# mux_board_final.net
KiCad netlist of a schematic drawn in EAGLE
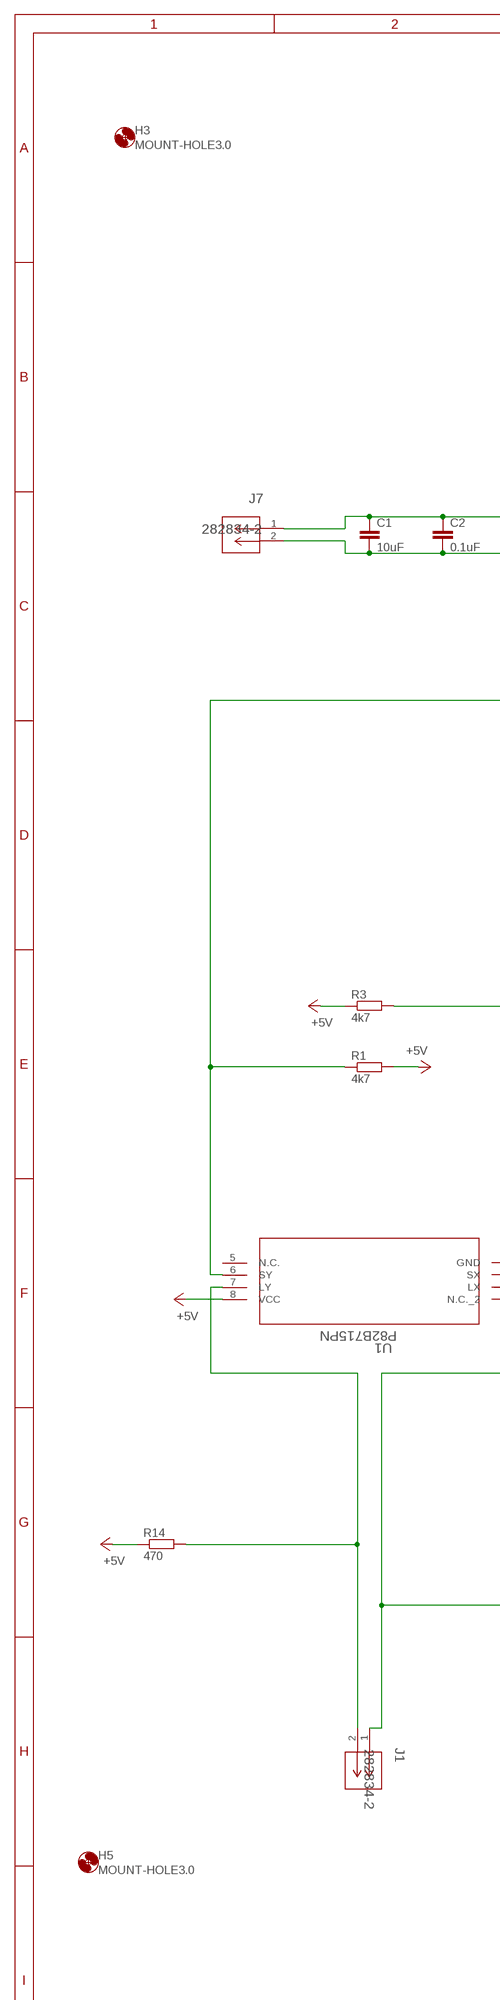
[diagram p0: schematic, sheet 1, part 1 of 2]
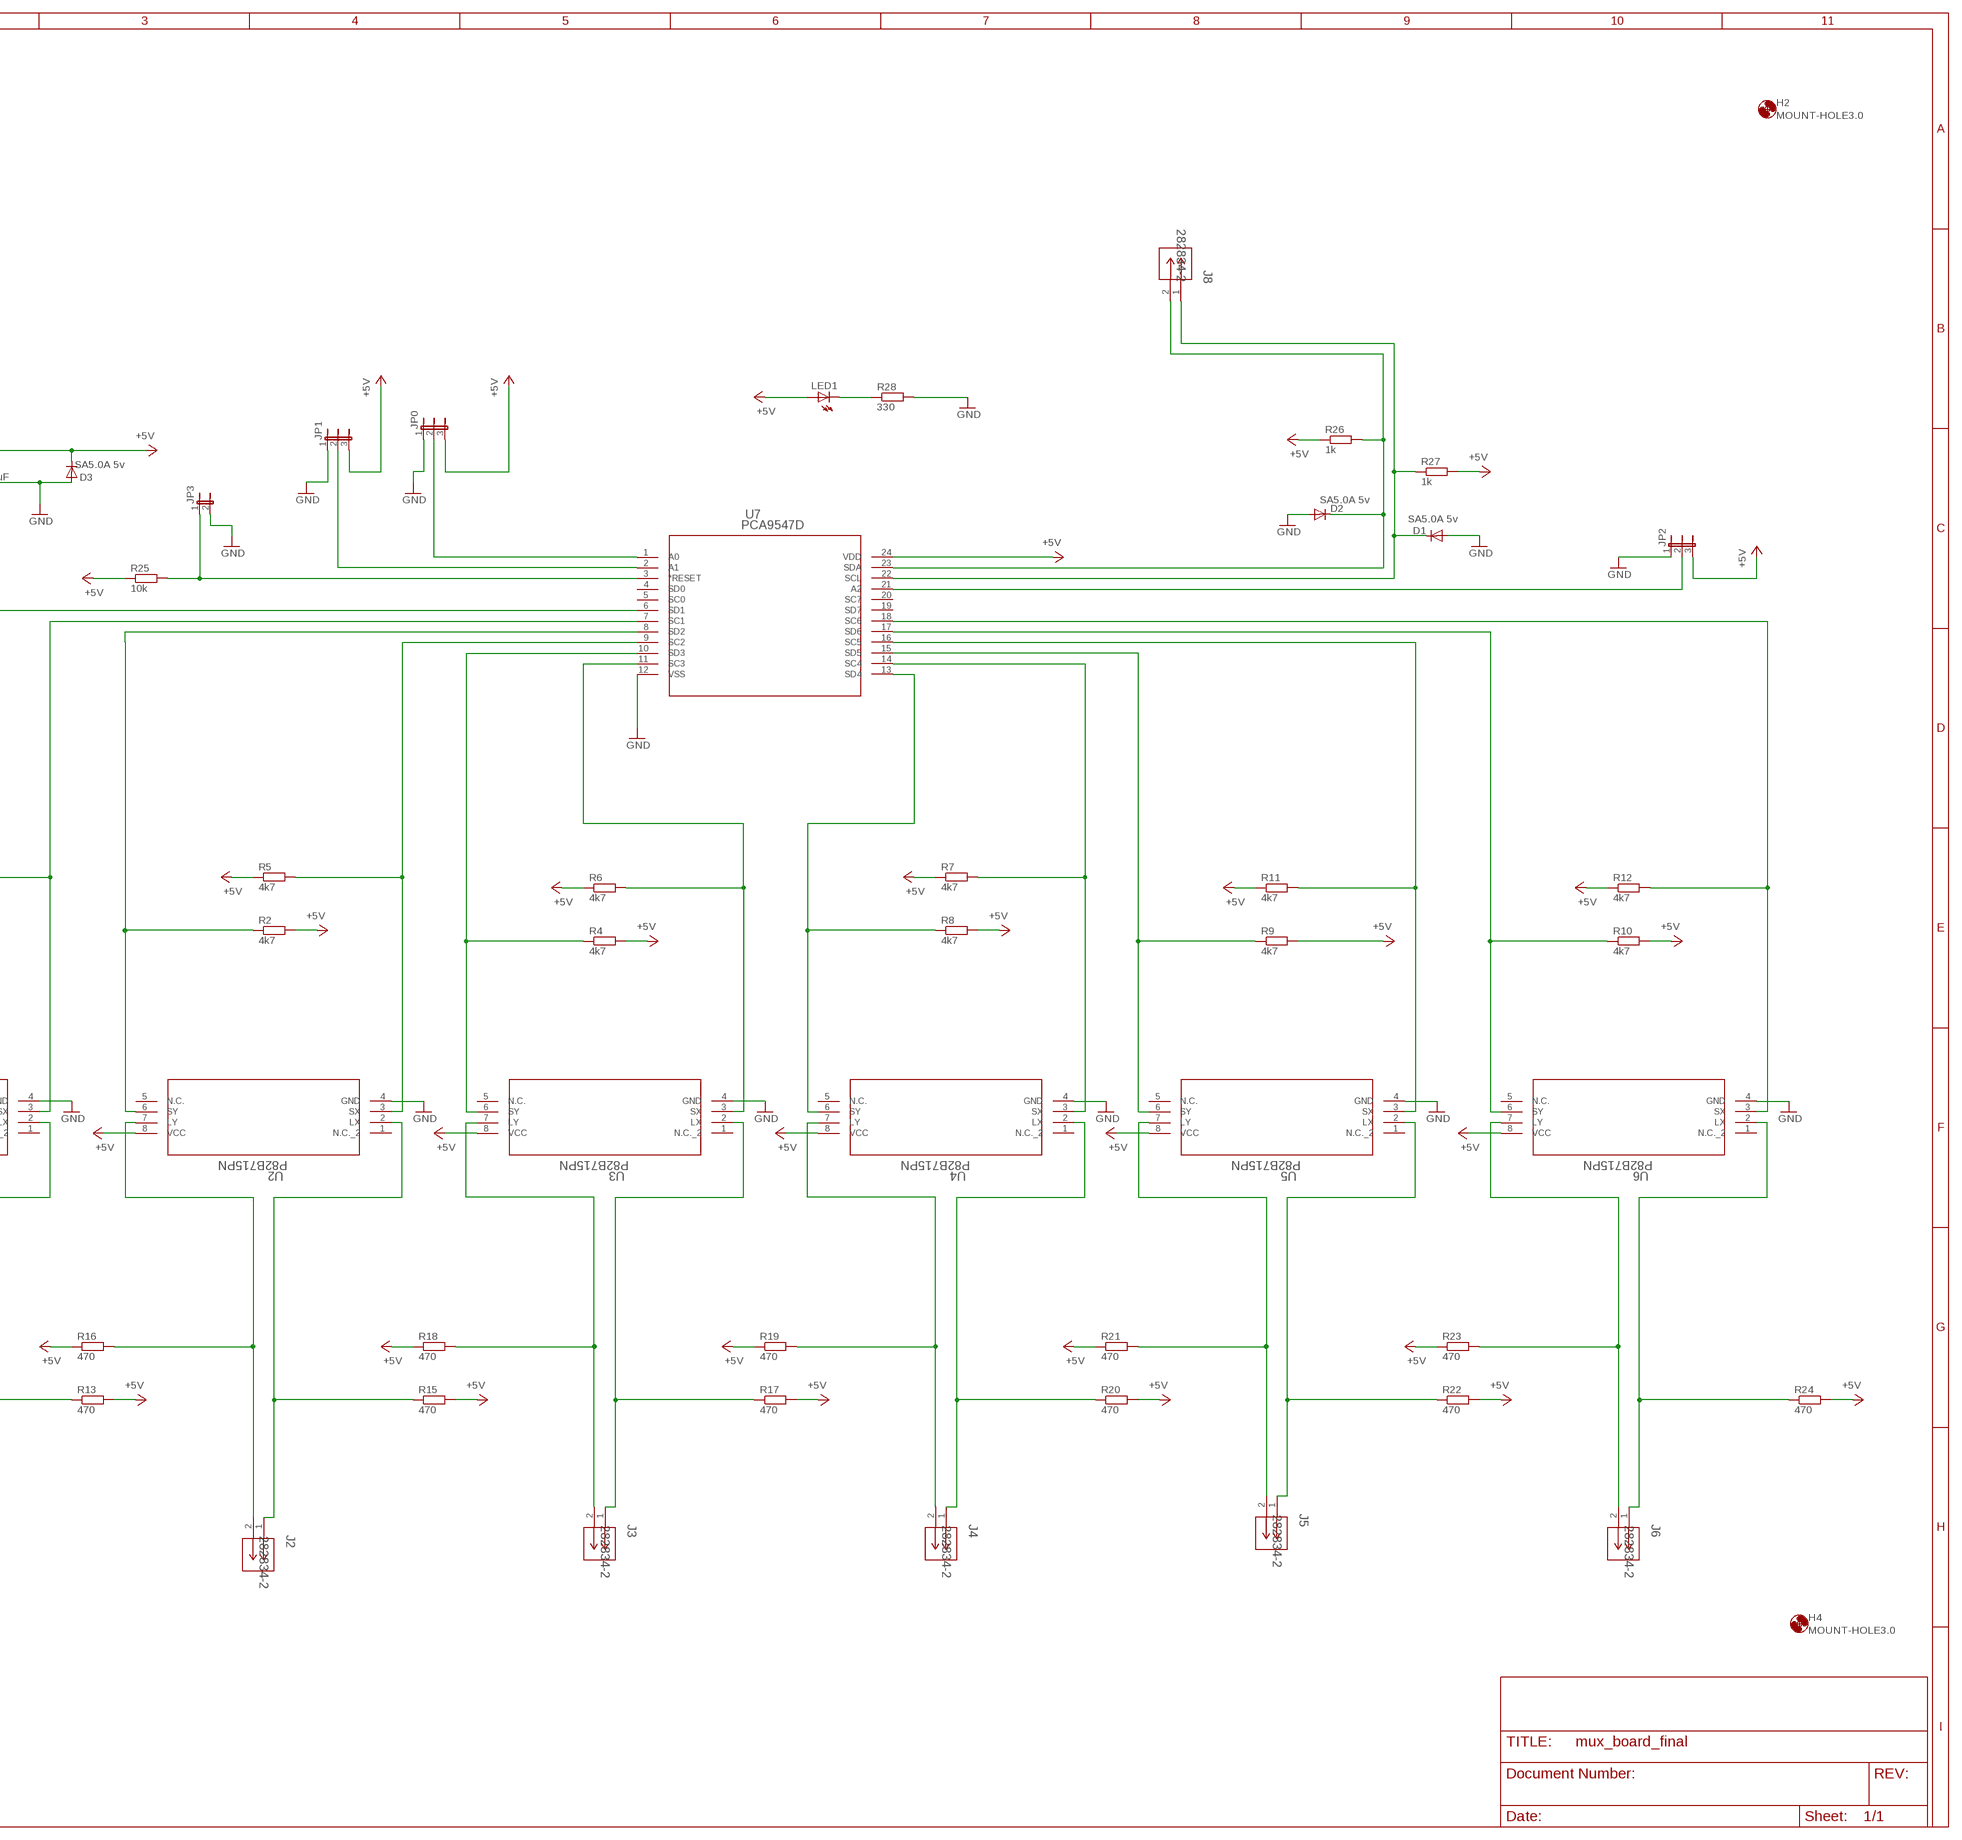
[diagram p1: schematic, sheet 1, part 2 of 2]

(export (version "E")
  (design (tool "Eeschema 10.0.6"))
  (components
    (comp (ref "C1")
      (value "10uF")
      (footprint "eagle-import:C025-025X050")
      (libsource (lib "eagle-import") (part "C-EU025-025X050"))
    )
    (comp (ref "C2")
      (value "0.1uF")
      (footprint "eagle-import:C025-025X050")
      (libsource (lib "eagle-import") (part "C-EU025-025X050"))
    )
    (comp (ref "D1")
      (value "SA5.0A 5v")
      (footprint "eagle-import:DO41-10")
      (libsource (lib "eagle-import") (part "1N4004"))
    )
    (comp (ref "D2")
      (value "SA5.0A 5v")
      (footprint "eagle-import:DO41-10")
      (libsource (lib "eagle-import") (part "1N4004"))
    )
    (comp (ref "D3")
      (value "SA5.0A 5v")
      (footprint "eagle-import:DO41-10")
      (libsource (lib "eagle-import") (part "1N4004"))
    )
    (comp (ref "H2")
      (value "MOUNT-HOLE3.0")
      (footprint "eagle-import:3,0")
      (libsource (lib "eagle-import") (part "MOUNT-HOLE3.0"))
    )
    (comp (ref "H3")
      (value "MOUNT-HOLE3.0")
      (footprint "eagle-import:3,0")
      (libsource (lib "eagle-import") (part "MOUNT-HOLE3.0"))
    )
    (comp (ref "H4")
      (value "MOUNT-HOLE3.0")
      (footprint "eagle-import:3,0")
      (libsource (lib "eagle-import") (part "MOUNT-HOLE3.0"))
    )
    (comp (ref "H5")
      (value "MOUNT-HOLE3.0")
      (footprint "eagle-import:3,0")
      (libsource (lib "eagle-import") (part "MOUNT-HOLE3.0"))
    )
    (comp (ref "J1")
      (value "282834-2")
      (footprint "eagle-import:CONN_282834-2")
      (fields (field (name "RSPARTNUMBER") "7100104"))
      (libsource (lib "eagle-import") (part "282834-2"))
    )
    (comp (ref "J2")
      (value "282834-2")
      (footprint "eagle-import:CONN_282834-2")
      (fields (field (name "RSPARTNUMBER") "7100104"))
      (libsource (lib "eagle-import") (part "282834-2"))
    )
    (comp (ref "J3")
      (value "282834-2")
      (footprint "eagle-import:CONN_282834-2")
      (fields (field (name "RSPARTNUMBER") "7100104"))
      (libsource (lib "eagle-import") (part "282834-2"))
    )
    (comp (ref "J4")
      (value "282834-2")
      (footprint "eagle-import:CONN_282834-2")
      (fields (field (name "RSPARTNUMBER") "7100104"))
      (libsource (lib "eagle-import") (part "282834-2"))
    )
    (comp (ref "J5")
      (value "282834-2")
      (footprint "eagle-import:CONN_282834-2")
      (fields (field (name "RSPARTNUMBER") "7100104"))
      (libsource (lib "eagle-import") (part "282834-2"))
    )
    (comp (ref "J6")
      (value "282834-2")
      (footprint "eagle-import:CONN_282834-2")
      (fields (field (name "RSPARTNUMBER") "7100104"))
      (libsource (lib "eagle-import") (part "282834-2"))
    )
    (comp (ref "J7")
      (value "282834-2")
      (footprint "eagle-import:CONN_282834-2")
      (fields (field (name "RSPARTNUMBER") "7100104"))
      (libsource (lib "eagle-import") (part "282834-2"))
    )
    (comp (ref "J8")
      (value "282834-2")
      (footprint "eagle-import:CONN_282834-2")
      (fields (field (name "RSPARTNUMBER") "7100104"))
      (libsource (lib "eagle-import") (part "282834-2"))
    )
    (comp (ref "JP0")
      (value "JP2E")
      (footprint "eagle-import:JP2")
      (libsource (lib "eagle-import") (part "JP2E"))
    )
    (comp (ref "JP1")
      (value "JP2E")
      (footprint "eagle-import:JP2")
      (libsource (lib "eagle-import") (part "JP2E"))
    )
    (comp (ref "JP2")
      (value "JP2E")
      (footprint "eagle-import:JP2")
      (libsource (lib "eagle-import") (part "JP2E"))
    )
    (comp (ref "JP3")
      (value "JP1E")
      (footprint "eagle-import:JP1")
      (libsource (lib "eagle-import") (part "JP1E"))
    )
    (comp (ref "LED1")
      (value "LED3MM")
      (footprint "eagle-import:LED3MM")
      (libsource (lib "eagle-import") (part "LED3MM"))
    )
    (comp (ref "R1")
      (value "4k7")
      (footprint "eagle-import:0204_7")
      (libsource (lib "eagle-import") (part "R-EU_0204/7"))
    )
    (comp (ref "R2")
      (value "4k7")
      (footprint "eagle-import:0204_7")
      (libsource (lib "eagle-import") (part "R-EU_0204/7"))
    )
    (comp (ref "R3")
      (value "4k7")
      (footprint "eagle-import:0204_7")
      (libsource (lib "eagle-import") (part "R-EU_0204/7"))
    )
    (comp (ref "R4")
      (value "4k7")
      (footprint "eagle-import:0204_7")
      (libsource (lib "eagle-import") (part "R-EU_0204/7"))
    )
    (comp (ref "R5")
      (value "4k7")
      (footprint "eagle-import:0204_7")
      (libsource (lib "eagle-import") (part "R-EU_0204/7"))
    )
    (comp (ref "R6")
      (value "4k7")
      (footprint "eagle-import:0204_7")
      (libsource (lib "eagle-import") (part "R-EU_0204/7"))
    )
    (comp (ref "R7")
      (value "4k7")
      (footprint "eagle-import:0204_7")
      (libsource (lib "eagle-import") (part "R-EU_0204/7"))
    )
    (comp (ref "R8")
      (value "4k7")
      (footprint "eagle-import:0204_7")
      (libsource (lib "eagle-import") (part "R-EU_0204/7"))
    )
    (comp (ref "R9")
      (value "4k7")
      (footprint "eagle-import:0204_7")
      (libsource (lib "eagle-import") (part "R-EU_0204/7"))
    )
    (comp (ref "R10")
      (value "4k7")
      (footprint "eagle-import:0204_7")
      (libsource (lib "eagle-import") (part "R-EU_0204/7"))
    )
    (comp (ref "R11")
      (value "4k7")
      (footprint "eagle-import:0204_7")
      (libsource (lib "eagle-import") (part "R-EU_0204/7"))
    )
    (comp (ref "R12")
      (value "4k7")
      (footprint "eagle-import:0204_7")
      (libsource (lib "eagle-import") (part "R-EU_0204/7"))
    )
    (comp (ref "R13")
      (value "470")
      (footprint "eagle-import:0204_7")
      (libsource (lib "eagle-import") (part "R-EU_0204/7"))
    )
    (comp (ref "R14")
      (value "470")
      (footprint "eagle-import:0204_7")
      (libsource (lib "eagle-import") (part "R-EU_0204/7"))
    )
    (comp (ref "R15")
      (value "470")
      (footprint "eagle-import:0204_7")
      (libsource (lib "eagle-import") (part "R-EU_0204/7"))
    )
    (comp (ref "R16")
      (value "470")
      (footprint "eagle-import:0204_7")
      (libsource (lib "eagle-import") (part "R-EU_0204/7"))
    )
    (comp (ref "R17")
      (value "470")
      (footprint "eagle-import:0204_7")
      (libsource (lib "eagle-import") (part "R-EU_0204/7"))
    )
    (comp (ref "R18")
      (value "470")
      (footprint "eagle-import:0204_7")
      (libsource (lib "eagle-import") (part "R-EU_0204/7"))
    )
    (comp (ref "R19")
      (value "470")
      (footprint "eagle-import:0204_7")
      (libsource (lib "eagle-import") (part "R-EU_0204/7"))
    )
    (comp (ref "R20")
      (value "470")
      (footprint "eagle-import:0204_7")
      (libsource (lib "eagle-import") (part "R-EU_0204/7"))
    )
    (comp (ref "R21")
      (value "470")
      (footprint "eagle-import:0204_7")
      (libsource (lib "eagle-import") (part "R-EU_0204/7"))
    )
    (comp (ref "R22")
      (value "470")
      (footprint "eagle-import:0204_7")
      (libsource (lib "eagle-import") (part "R-EU_0204/7"))
    )
    (comp (ref "R23")
      (value "470")
      (footprint "eagle-import:0204_7")
      (libsource (lib "eagle-import") (part "R-EU_0204/7"))
    )
    (comp (ref "R24")
      (value "470")
      (footprint "eagle-import:0204_7")
      (libsource (lib "eagle-import") (part "R-EU_0204/7"))
    )
    (comp (ref "R25")
      (value "10k")
      (footprint "eagle-import:0204_7")
      (libsource (lib "eagle-import") (part "R-EU_0204/7"))
    )
    (comp (ref "R26")
      (value "1k")
      (footprint "eagle-import:0204_7")
      (libsource (lib "eagle-import") (part "R-EU_0204/7"))
    )
    (comp (ref "R27")
      (value "1k")
      (footprint "eagle-import:0204_7")
      (libsource (lib "eagle-import") (part "R-EU_0204/7"))
    )
    (comp (ref "R28")
      (value "330")
      (footprint "eagle-import:0204_7")
      (libsource (lib "eagle-import") (part "R-EU_0204/7"))
    )
    (comp (ref "U1")
      (value "P82B715PN")
      (footprint "eagle-import:SOT97-1")
      (fields (field (name "RSPARTNUMBER") "821784"))
      (libsource (lib "eagle-import") (part "P82B715PN"))
    )
    (comp (ref "U2")
      (value "P82B715PN")
      (footprint "eagle-import:SOT97-1")
      (fields (field (name "RSPARTNUMBER") "821784"))
      (libsource (lib "eagle-import") (part "P82B715PN"))
    )
    (comp (ref "U3")
      (value "P82B715PN")
      (footprint "eagle-import:SOT97-1")
      (fields (field (name "RSPARTNUMBER") "821784"))
      (libsource (lib "eagle-import") (part "P82B715PN"))
    )
    (comp (ref "U4")
      (value "P82B715PN")
      (footprint "eagle-import:SOT97-1")
      (fields (field (name "RSPARTNUMBER") "821784"))
      (libsource (lib "eagle-import") (part "P82B715PN"))
    )
    (comp (ref "U5")
      (value "P82B715PN")
      (footprint "eagle-import:SOT97-1")
      (fields (field (name "RSPARTNUMBER") "821784"))
      (libsource (lib "eagle-import") (part "P82B715PN"))
    )
    (comp (ref "U6")
      (value "P82B715PN")
      (footprint "eagle-import:SOT97-1")
      (fields (field (name "RSPARTNUMBER") "821784"))
      (libsource (lib "eagle-import") (part "P82B715PN"))
    )
    (comp (ref "U7")
      (value "PCA9547D")
      (footprint "eagle-import:SOT137-1")
      (fields (field (name "RSPARTNUMBER") "7258877"))
      (libsource (lib "eagle-import") (part "PCA9547D"))
    )
  )
  (nets
    (net (code "1") (name "+5V") (class "Default")
      (node (ref "C1") (pin "1") (pinfunction "1_1") (pintype "passive"))
      (node (ref "C2") (pin "1") (pinfunction "1_1") (pintype "passive"))
      (node (ref "D3") (pin "C") (pinfunction "C_C") (pintype "passive"))
      (node (ref "J7") (pin "1") (pinfunction "1_1") (pintype "passive"))
      (node (ref "JP0") (pin "3") (pinfunction "3_3") (pintype "passive"))
      (node (ref "JP1") (pin "3") (pinfunction "3_3") (pintype "passive"))
      (node (ref "JP2") (pin "3") (pinfunction "3_3") (pintype "passive"))
      (node (ref "LED1") (pin "A") (pinfunction "A_A") (pintype "passive"))
      (node (ref "R1") (pin "2") (pinfunction "2_2") (pintype "passive"))
      (node (ref "R10") (pin "2") (pinfunction "2_2") (pintype "passive"))
      (node (ref "R11") (pin "1") (pinfunction "1_1") (pintype "passive"))
      (node (ref "R12") (pin "1") (pinfunction "1_1") (pintype "passive"))
      (node (ref "R13") (pin "2") (pinfunction "2_2") (pintype "passive"))
      (node (ref "R14") (pin "1") (pinfunction "1_1") (pintype "passive"))
      (node (ref "R15") (pin "2") (pinfunction "2_2") (pintype "passive"))
      (node (ref "R16") (pin "1") (pinfunction "1_1") (pintype "passive"))
      (node (ref "R17") (pin "2") (pinfunction "2_2") (pintype "passive"))
      (node (ref "R18") (pin "1") (pinfunction "1_1") (pintype "passive"))
      (node (ref "R19") (pin "1") (pinfunction "1_1") (pintype "passive"))
      (node (ref "R2") (pin "2") (pinfunction "2_2") (pintype "passive"))
      (node (ref "R20") (pin "2") (pinfunction "2_2") (pintype "passive"))
      (node (ref "R21") (pin "1") (pinfunction "1_1") (pintype "passive"))
      (node (ref "R22") (pin "2") (pinfunction "2_2") (pintype "passive"))
      (node (ref "R23") (pin "1") (pinfunction "1_1") (pintype "passive"))
      (node (ref "R24") (pin "2") (pinfunction "2_2") (pintype "passive"))
      (node (ref "R25") (pin "1") (pinfunction "1_1") (pintype "passive"))
      (node (ref "R26") (pin "1") (pinfunction "1_1") (pintype "passive"))
      (node (ref "R27") (pin "2") (pinfunction "2_2") (pintype "passive"))
      (node (ref "R3") (pin "1") (pinfunction "1_1") (pintype "passive"))
      (node (ref "R4") (pin "2") (pinfunction "2_2") (pintype "passive"))
      (node (ref "R5") (pin "1") (pinfunction "1_1") (pintype "passive"))
      (node (ref "R6") (pin "1") (pinfunction "1_1") (pintype "passive"))
      (node (ref "R7") (pin "1") (pinfunction "1_1") (pintype "passive"))
      (node (ref "R8") (pin "2") (pinfunction "2_2") (pintype "passive"))
      (node (ref "R9") (pin "2") (pinfunction "2_2") (pintype "passive"))
      (node (ref "U1") (pin "8") (pinfunction "VCC_8") (pintype "passive"))
      (node (ref "U2") (pin "8") (pinfunction "VCC_8") (pintype "passive"))
      (node (ref "U3") (pin "8") (pinfunction "VCC_8") (pintype "passive"))
      (node (ref "U4") (pin "8") (pinfunction "VCC_8") (pintype "passive"))
      (node (ref "U5") (pin "8") (pinfunction "VCC_8") (pintype "passive"))
      (node (ref "U6") (pin "8") (pinfunction "VCC_8") (pintype "passive"))
      (node (ref "U7") (pin "24") (pinfunction "VDD_24") (pintype "passive"))
    )
    (net (code "2") (name "GND") (class "Default")
      (node (ref "C1") (pin "2") (pinfunction "2_2") (pintype "passive"))
      (node (ref "C2") (pin "2") (pinfunction "2_2") (pintype "passive"))
      (node (ref "D1") (pin "A") (pinfunction "A_A") (pintype "passive"))
      (node (ref "D2") (pin "A") (pinfunction "A_A") (pintype "passive"))
      (node (ref "D3") (pin "A") (pinfunction "A_A") (pintype "passive"))
      (node (ref "J7") (pin "2") (pinfunction "2_2") (pintype "passive"))
      (node (ref "JP0") (pin "1") (pinfunction "1_1") (pintype "passive"))
      (node (ref "JP1") (pin "1") (pinfunction "1_1") (pintype "passive"))
      (node (ref "JP2") (pin "1") (pinfunction "1_1") (pintype "passive"))
      (node (ref "JP3") (pin "2") (pinfunction "2_2") (pintype "passive"))
      (node (ref "R28") (pin "2") (pinfunction "2_2") (pintype "passive"))
      (node (ref "U1") (pin "4") (pinfunction "GND_4") (pintype "passive"))
      (node (ref "U2") (pin "4") (pinfunction "GND_4") (pintype "passive"))
      (node (ref "U3") (pin "4") (pinfunction "GND_4") (pintype "passive"))
      (node (ref "U4") (pin "4") (pinfunction "GND_4") (pintype "passive"))
      (node (ref "U5") (pin "4") (pinfunction "GND_4") (pintype "passive"))
      (node (ref "U6") (pin "4") (pinfunction "GND_4") (pintype "passive"))
      (node (ref "U7") (pin "12") (pinfunction "VSS_12") (pintype "passive"))
    )
    (net (code "3") (name "Net-(LED1-C)") (class "Default")
      (node (ref "LED1") (pin "K") (pinfunction "C_K") (pintype "passive"))
      (node (ref "R28") (pin "1") (pinfunction "1_1") (pintype "passive"))
    )
    (net (code "4") (name "Net-(U1-LX)") (class "Default")
      (node (ref "J1") (pin "1") (pinfunction "1_1") (pintype "passive"))
      (node (ref "R13") (pin "1") (pinfunction "1_1") (pintype "passive"))
      (node (ref "U1") (pin "2") (pinfunction "LX_2") (pintype "passive"))
    )
    (net (code "5") (name "Net-(U1-LY)") (class "Default")
      (node (ref "J1") (pin "2") (pinfunction "2_2") (pintype "passive"))
      (node (ref "R14") (pin "2") (pinfunction "2_2") (pintype "passive"))
      (node (ref "U1") (pin "7") (pinfunction "LY_7") (pintype "passive"))
    )
    (net (code "6") (name "Net-(U1-SX)") (class "Default")
      (node (ref "R3") (pin "2") (pinfunction "2_2") (pintype "passive"))
      (node (ref "U1") (pin "3") (pinfunction "SX_3") (pintype "passive"))
      (node (ref "U7") (pin "7") (pinfunction "SC1_7") (pintype "passive"))
    )
    (net (code "7") (name "Net-(U1-SY)") (class "Default")
      (node (ref "R1") (pin "1") (pinfunction "1_1") (pintype "passive"))
      (node (ref "U1") (pin "6") (pinfunction "SY_6") (pintype "passive"))
      (node (ref "U7") (pin "6") (pinfunction "SD1_6") (pintype "passive"))
    )
    (net (code "8") (name "Net-(U2-LX)") (class "Default")
      (node (ref "J2") (pin "1") (pinfunction "1_1") (pintype "passive"))
      (node (ref "R15") (pin "1") (pinfunction "1_1") (pintype "passive"))
      (node (ref "U2") (pin "2") (pinfunction "LX_2") (pintype "passive"))
    )
    (net (code "9") (name "Net-(U2-LY)") (class "Default")
      (node (ref "J2") (pin "2") (pinfunction "2_2") (pintype "passive"))
      (node (ref "R16") (pin "2") (pinfunction "2_2") (pintype "passive"))
      (node (ref "U2") (pin "7") (pinfunction "LY_7") (pintype "passive"))
    )
    (net (code "10") (name "Net-(U2-SX)") (class "Default")
      (node (ref "R5") (pin "2") (pinfunction "2_2") (pintype "passive"))
      (node (ref "U2") (pin "3") (pinfunction "SX_3") (pintype "passive"))
      (node (ref "U7") (pin "9") (pinfunction "SC2_9") (pintype "passive"))
    )
    (net (code "11") (name "Net-(U2-SY)") (class "Default")
      (node (ref "R2") (pin "1") (pinfunction "1_1") (pintype "passive"))
      (node (ref "U2") (pin "6") (pinfunction "SY_6") (pintype "passive"))
      (node (ref "U7") (pin "8") (pinfunction "SD2_8") (pintype "passive"))
    )
    (net (code "12") (name "Net-(U3-LX)") (class "Default")
      (node (ref "J3") (pin "1") (pinfunction "1_1") (pintype "passive"))
      (node (ref "R17") (pin "1") (pinfunction "1_1") (pintype "passive"))
      (node (ref "U3") (pin "2") (pinfunction "LX_2") (pintype "passive"))
    )
    (net (code "13") (name "Net-(U3-LY)") (class "Default")
      (node (ref "J3") (pin "2") (pinfunction "2_2") (pintype "passive"))
      (node (ref "R18") (pin "2") (pinfunction "2_2") (pintype "passive"))
      (node (ref "U3") (pin "7") (pinfunction "LY_7") (pintype "passive"))
    )
    (net (code "14") (name "Net-(U3-SX)") (class "Default")
      (node (ref "R6") (pin "2") (pinfunction "2_2") (pintype "passive"))
      (node (ref "U3") (pin "3") (pinfunction "SX_3") (pintype "passive"))
      (node (ref "U7") (pin "11") (pinfunction "SC3_11") (pintype "passive"))
    )
    (net (code "15") (name "Net-(U3-SY)") (class "Default")
      (node (ref "R4") (pin "1") (pinfunction "1_1") (pintype "passive"))
      (node (ref "U3") (pin "6") (pinfunction "SY_6") (pintype "passive"))
      (node (ref "U7") (pin "10") (pinfunction "SD3_10") (pintype "passive"))
    )
    (net (code "16") (name "Net-(U4-LX)") (class "Default")
      (node (ref "J4") (pin "1") (pinfunction "1_1") (pintype "passive"))
      (node (ref "R20") (pin "1") (pinfunction "1_1") (pintype "passive"))
      (node (ref "U4") (pin "2") (pinfunction "LX_2") (pintype "passive"))
    )
    (net (code "17") (name "Net-(U4-LY)") (class "Default")
      (node (ref "J4") (pin "2") (pinfunction "2_2") (pintype "passive"))
      (node (ref "R19") (pin "2") (pinfunction "2_2") (pintype "passive"))
      (node (ref "U4") (pin "7") (pinfunction "LY_7") (pintype "passive"))
    )
    (net (code "18") (name "Net-(U4-SX)") (class "Default")
      (node (ref "R7") (pin "2") (pinfunction "2_2") (pintype "passive"))
      (node (ref "U4") (pin "3") (pinfunction "SX_3") (pintype "passive"))
      (node (ref "U7") (pin "14") (pinfunction "SC4_14") (pintype "passive"))
    )
    (net (code "19") (name "Net-(U4-SY)") (class "Default")
      (node (ref "R8") (pin "1") (pinfunction "1_1") (pintype "passive"))
      (node (ref "U4") (pin "6") (pinfunction "SY_6") (pintype "passive"))
      (node (ref "U7") (pin "13") (pinfunction "SD4_13") (pintype "passive"))
    )
    (net (code "20") (name "Net-(U5-LX)") (class "Default")
      (node (ref "J5") (pin "1") (pinfunction "1_1") (pintype "passive"))
      (node (ref "R22") (pin "1") (pinfunction "1_1") (pintype "passive"))
      (node (ref "U5") (pin "2") (pinfunction "LX_2") (pintype "passive"))
    )
    (net (code "21") (name "Net-(U5-LY)") (class "Default")
      (node (ref "J5") (pin "2") (pinfunction "2_2") (pintype "passive"))
      (node (ref "R21") (pin "2") (pinfunction "2_2") (pintype "passive"))
      (node (ref "U5") (pin "7") (pinfunction "LY_7") (pintype "passive"))
    )
    (net (code "22") (name "Net-(U5-SX)") (class "Default")
      (node (ref "R11") (pin "2") (pinfunction "2_2") (pintype "passive"))
      (node (ref "U5") (pin "3") (pinfunction "SX_3") (pintype "passive"))
      (node (ref "U7") (pin "16") (pinfunction "SC5_16") (pintype "passive"))
    )
    (net (code "23") (name "Net-(U5-SY)") (class "Default")
      (node (ref "R9") (pin "1") (pinfunction "1_1") (pintype "passive"))
      (node (ref "U5") (pin "6") (pinfunction "SY_6") (pintype "passive"))
      (node (ref "U7") (pin "15") (pinfunction "SD5_15") (pintype "passive"))
    )
    (net (code "24") (name "Net-(U6-LX)") (class "Default")
      (node (ref "J6") (pin "1") (pinfunction "1_1") (pintype "passive"))
      (node (ref "R24") (pin "1") (pinfunction "1_1") (pintype "passive"))
      (node (ref "U6") (pin "2") (pinfunction "LX_2") (pintype "passive"))
    )
    (net (code "25") (name "Net-(U6-LY)") (class "Default")
      (node (ref "J6") (pin "2") (pinfunction "2_2") (pintype "passive"))
      (node (ref "R23") (pin "2") (pinfunction "2_2") (pintype "passive"))
      (node (ref "U6") (pin "7") (pinfunction "LY_7") (pintype "passive"))
    )
    (net (code "26") (name "Net-(U6-SX)") (class "Default")
      (node (ref "R12") (pin "2") (pinfunction "2_2") (pintype "passive"))
      (node (ref "U6") (pin "3") (pinfunction "SX_3") (pintype "passive"))
      (node (ref "U7") (pin "18") (pinfunction "SC6_18") (pintype "passive"))
    )
    (net (code "27") (name "Net-(U6-SY)") (class "Default")
      (node (ref "R10") (pin "1") (pinfunction "1_1") (pintype "passive"))
      (node (ref "U6") (pin "6") (pinfunction "SY_6") (pintype "passive"))
      (node (ref "U7") (pin "17") (pinfunction "SD6_17") (pintype "passive"))
    )
    (net (code "28") (name "Net-(U7-*RESET)") (class "Default")
      (node (ref "JP3") (pin "1") (pinfunction "1_1") (pintype "passive"))
      (node (ref "R25") (pin "2") (pinfunction "2_2") (pintype "passive"))
      (node (ref "U7") (pin "3") (pinfunction "*RESET_3") (pintype "passive"))
    )
    (net (code "29") (name "Net-(U7-A0)") (class "Default")
      (node (ref "JP0") (pin "2") (pinfunction "2_2") (pintype "passive"))
      (node (ref "U7") (pin "1") (pinfunction "A0_1") (pintype "passive"))
    )
    (net (code "30") (name "Net-(U7-A1)") (class "Default")
      (node (ref "JP1") (pin "2") (pinfunction "2_2") (pintype "passive"))
      (node (ref "U7") (pin "2") (pinfunction "A1_2") (pintype "passive"))
    )
    (net (code "31") (name "Net-(U7-A2)") (class "Default")
      (node (ref "JP2") (pin "2") (pinfunction "2_2") (pintype "passive"))
      (node (ref "U7") (pin "21") (pinfunction "A2_21") (pintype "passive"))
    )
    (net (code "32") (name "Net-(U7-SCL)") (class "Default")
      (node (ref "D1") (pin "C") (pinfunction "C_C") (pintype "passive"))
      (node (ref "J8") (pin "1") (pinfunction "1_1") (pintype "passive"))
      (node (ref "R27") (pin "1") (pinfunction "1_1") (pintype "passive"))
      (node (ref "U7") (pin "22") (pinfunction "SCL_22") (pintype "passive"))
    )
    (net (code "33") (name "Net-(U7-SDA)") (class "Default")
      (node (ref "D2") (pin "C") (pinfunction "C_C") (pintype "passive"))
      (node (ref "J8") (pin "2") (pinfunction "2_2") (pintype "passive"))
      (node (ref "R26") (pin "2") (pinfunction "2_2") (pintype "passive"))
      (node (ref "U7") (pin "23") (pinfunction "SDA_23") (pintype "passive"))
    )
    (net (code "34") (name "unconnected-(U1-N.C.-Pad5)") (class "Default")
      (node (ref "U1") (pin "5") (pinfunction "N.C._5") (pintype "passive"))
    )
    (net (code "35") (name "unconnected-(U1-N.C._2-Pad1)") (class "Default")
      (node (ref "U1") (pin "1") (pinfunction "N.C._2_1") (pintype "passive"))
    )
    (net (code "36") (name "unconnected-(U2-N.C.-Pad5)") (class "Default")
      (node (ref "U2") (pin "5") (pinfunction "N.C._5") (pintype "passive"))
    )
    (net (code "37") (name "unconnected-(U2-N.C._2-Pad1)") (class "Default")
      (node (ref "U2") (pin "1") (pinfunction "N.C._2_1") (pintype "passive"))
    )
    (net (code "38") (name "unconnected-(U3-N.C.-Pad5)") (class "Default")
      (node (ref "U3") (pin "5") (pinfunction "N.C._5") (pintype "passive"))
    )
    (net (code "39") (name "unconnected-(U3-N.C._2-Pad1)") (class "Default")
      (node (ref "U3") (pin "1") (pinfunction "N.C._2_1") (pintype "passive"))
    )
    (net (code "40") (name "unconnected-(U4-N.C.-Pad5)") (class "Default")
      (node (ref "U4") (pin "5") (pinfunction "N.C._5") (pintype "passive"))
    )
    (net (code "41") (name "unconnected-(U4-N.C._2-Pad1)") (class "Default")
      (node (ref "U4") (pin "1") (pinfunction "N.C._2_1") (pintype "passive"))
    )
    (net (code "42") (name "unconnected-(U5-N.C.-Pad5)") (class "Default")
      (node (ref "U5") (pin "5") (pinfunction "N.C._5") (pintype "passive"))
    )
    (net (code "43") (name "unconnected-(U5-N.C._2-Pad1)") (class "Default")
      (node (ref "U5") (pin "1") (pinfunction "N.C._2_1") (pintype "passive"))
    )
    (net (code "44") (name "unconnected-(U6-N.C.-Pad5)") (class "Default")
      (node (ref "U6") (pin "5") (pinfunction "N.C._5") (pintype "passive"))
    )
    (net (code "45") (name "unconnected-(U6-N.C._2-Pad1)") (class "Default")
      (node (ref "U6") (pin "1") (pinfunction "N.C._2_1") (pintype "passive"))
    )
    (net (code "46") (name "unconnected-(U7-SC0-Pad5)") (class "Default")
      (node (ref "U7") (pin "5") (pinfunction "SC0_5") (pintype "passive"))
    )
    (net (code "47") (name "unconnected-(U7-SC7-Pad20)") (class "Default")
      (node (ref "U7") (pin "20") (pinfunction "SC7_20") (pintype "passive"))
    )
    (net (code "48") (name "unconnected-(U7-SD0-Pad4)") (class "Default")
      (node (ref "U7") (pin "4") (pinfunction "SD0_4") (pintype "passive"))
    )
    (net (code "49") (name "unconnected-(U7-SD7-Pad19)") (class "Default")
      (node (ref "U7") (pin "19") (pinfunction "SD7_19") (pintype "passive"))
    )
  )
)
